# Receiver.net
KiCad netlist of a schematic drawn in Altium Designer
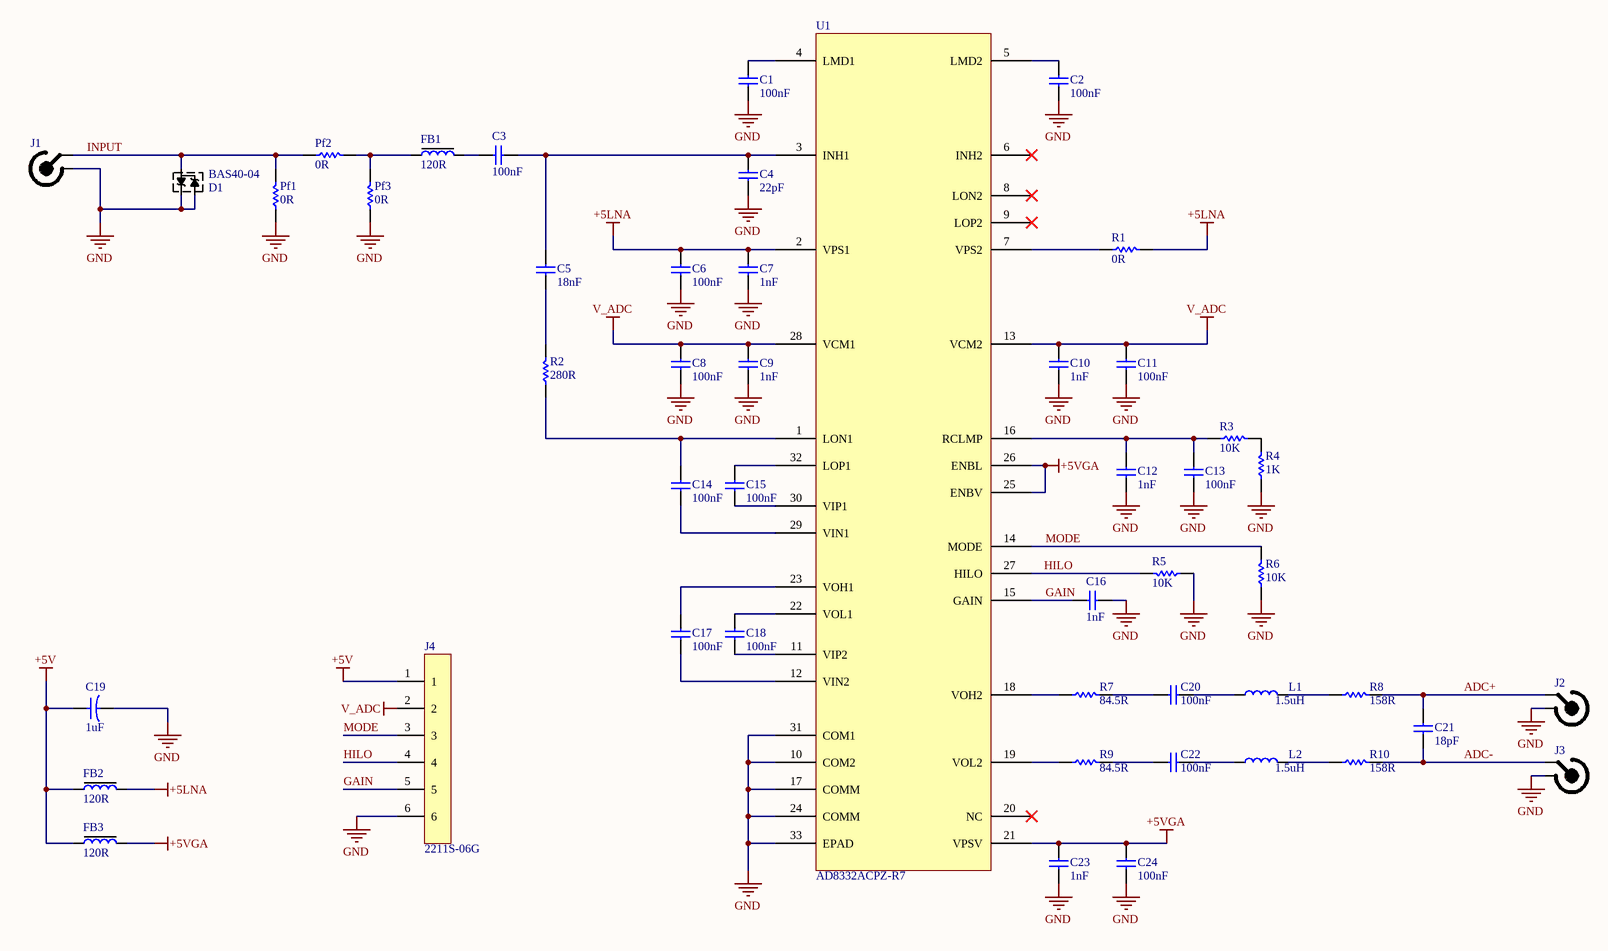
[diagram p0: Receiver.SchDoc]

(export (version "E")
  (design (tool "Eeschema 10.0.6"))
  (components
    (comp (ref "C1")
      (value "100nF")
      (footprint "CAP 0603/1608")
      (description "CAPACITOR 0603 100nF 10% 50V")
      (fields
        (field (name "MANUFACTURER") "Murata")
        (field (name "MANUFACTURER PART NUMBER") "GCJ188R71H104KA12D")
      )
      (libsource (lib "Component Library") (part "GCJ188R71H104KA12D"))
    )
    (comp (ref "C2")
      (value "100nF")
      (footprint "CAP 0603/1608")
      (description "CAPACITOR 0603 100nF 10% 50V")
      (fields
        (field (name "MANUFACTURER") "Murata")
        (field (name "MANUFACTURER PART NUMBER") "GCJ188R71H104KA12D")
      )
      (libsource (lib "Component Library") (part "GCJ188R71H104KA12D"))
    )
    (comp (ref "C3")
      (value "100nF")
      (footprint "CAP 0603/1608")
      (description "CAPACITOR 0603 100nF 10% 50V")
      (fields
        (field (name "MANUFACTURER") "Murata")
        (field (name "MANUFACTURER PART NUMBER") "GCJ188R71H104KA12D")
      )
      (libsource (lib "Component Library") (part "GCJ188R71H104KA12D"))
    )
    (comp (ref "C4")
      (value "22pF")
      (footprint "CAP 0603/1608")
      (description "CAPACITOR 0603 22 pF 50 V  5%, C0G / NP0")
      (fields
        (field (name "MANUFACTURER") "TDK")
        (field (name "MANUFACTURER PART NUMBER") "C1608C0G1H220J080AA")
      )
      (libsource (lib "Component Library") (part "C1608C0G1H220J080AA"))
    )
    (comp (ref "C5")
      (value "18nF")
      (footprint "CAP 0603/1608")
      (description "CAPACITOR 0603 18nF 35V NP0")
      (fields
        (field (name "MANUFACTURER") "TDK")
        (field (name "MANUFACTURER PART NUMBER") "C1608C0G1V183J080AC")
      )
      (libsource (lib "Component Library") (part "C1608C0G1V183J080AC"))
    )
    (comp (ref "C6")
      (value "100nF")
      (footprint "CAP 0603/1608")
      (description "CAPACITOR 0603 100nF 10% 50V")
      (fields
        (field (name "MANUFACTURER") "Murata")
        (field (name "MANUFACTURER PART NUMBER") "GCJ188R71H104KA12D")
      )
      (libsource (lib "Component Library") (part "GCJ188R71H104KA12D"))
    )
    (comp (ref "C7")
      (value "1nF")
      (footprint "CAP 0603/1608")
      (description "CAPACITOR 0603 1nF 100V C0G/NP0")
      (fields
        (field (name "MANUFACTURER") "Murata")
        (field (name "MANUFACTURER PART NUMBER") "GRM1885C2A102JA01D")
      )
      (libsource (lib "Component Library") (part "GRM1885C2A102JA01D"))
    )
    (comp (ref "C8")
      (value "100nF")
      (footprint "CAP 0603/1608")
      (description "CAPACITOR 0603 100nF 10% 50V")
      (fields
        (field (name "MANUFACTURER") "Murata")
        (field (name "MANUFACTURER PART NUMBER") "GCJ188R71H104KA12D")
      )
      (libsource (lib "Component Library") (part "GCJ188R71H104KA12D"))
    )
    (comp (ref "C9")
      (value "1nF")
      (footprint "CAP 0603/1608")
      (description "CAPACITOR 0603 1nF 100V C0G/NP0")
      (fields
        (field (name "MANUFACTURER") "Murata")
        (field (name "MANUFACTURER PART NUMBER") "GRM1885C2A102JA01D")
      )
      (libsource (lib "Component Library") (part "GRM1885C2A102JA01D"))
    )
    (comp (ref "C10")
      (value "1nF")
      (footprint "CAP 0603/1608")
      (description "CAPACITOR 0603 1nF 100V C0G/NP0")
      (fields
        (field (name "MANUFACTURER") "Murata")
        (field (name "MANUFACTURER PART NUMBER") "GRM1885C2A102JA01D")
      )
      (libsource (lib "Component Library") (part "GRM1885C2A102JA01D"))
    )
    (comp (ref "C11")
      (value "100nF")
      (footprint "CAP 0603/1608")
      (description "CAPACITOR 0603 100nF 10% 50V")
      (fields
        (field (name "MANUFACTURER") "Murata")
        (field (name "MANUFACTURER PART NUMBER") "GCJ188R71H104KA12D")
      )
      (libsource (lib "Component Library") (part "GCJ188R71H104KA12D"))
    )
    (comp (ref "C12")
      (value "1nF")
      (footprint "CAP 0603/1608")
      (description "CAPACITOR 0603 1nF 100V C0G/NP0")
      (fields
        (field (name "MANUFACTURER") "Murata")
        (field (name "MANUFACTURER PART NUMBER") "GRM1885C2A102JA01D")
      )
      (libsource (lib "Component Library") (part "GRM1885C2A102JA01D"))
    )
    (comp (ref "C13")
      (value "100nF")
      (footprint "CAP 0603/1608")
      (description "CAPACITOR 0603 100nF 10% 50V")
      (fields
        (field (name "MANUFACTURER") "Murata")
        (field (name "MANUFACTURER PART NUMBER") "GCJ188R71H104KA12D")
      )
      (libsource (lib "Component Library") (part "GCJ188R71H104KA12D"))
    )
    (comp (ref "C14")
      (value "100nF")
      (footprint "CAP 0603/1608")
      (description "CAPACITOR 0603 100nF 10% 50V")
      (fields
        (field (name "MANUFACTURER") "Murata")
        (field (name "MANUFACTURER PART NUMBER") "GCJ188R71H104KA12D")
      )
      (libsource (lib "Component Library") (part "GCJ188R71H104KA12D"))
    )
    (comp (ref "C15")
      (value "100nF")
      (footprint "CAP 0603/1608")
      (description "CAPACITOR 0603 100nF 10% 50V")
      (fields
        (field (name "MANUFACTURER") "Murata")
        (field (name "MANUFACTURER PART NUMBER") "GCJ188R71H104KA12D")
      )
      (libsource (lib "Component Library") (part "GCJ188R71H104KA12D"))
    )
    (comp (ref "C16")
      (value "1nF")
      (footprint "CAP 0603/1608")
      (description "CAPACITOR 0603 1nF 100V C0G/NP0")
      (fields
        (field (name "MANUFACTURER") "Murata")
        (field (name "MANUFACTURER PART NUMBER") "GRM1885C2A102JA01D")
      )
      (libsource (lib "Component Library") (part "GRM1885C2A102JA01D"))
    )
    (comp (ref "C17")
      (value "100nF")
      (footprint "CAP 0603/1608")
      (description "CAPACITOR 0603 100nF 10% 50V")
      (fields
        (field (name "MANUFACTURER") "Murata")
        (field (name "MANUFACTURER PART NUMBER") "GCJ188R71H104KA12D")
      )
      (libsource (lib "Component Library") (part "GCJ188R71H104KA12D"))
    )
    (comp (ref "C18")
      (value "100nF")
      (footprint "CAP 0603/1608")
      (description "CAPACITOR 0603 100nF 10% 50V")
      (fields
        (field (name "MANUFACTURER") "Murata")
        (field (name "MANUFACTURER PART NUMBER") "GCJ188R71H104KA12D")
      )
      (libsource (lib "Component Library") (part "GCJ188R71H104KA12D"))
    )
    (comp (ref "C19")
      (value "1uF")
      (footprint "CAP CASE A")
      (description "CAPACITOR TANT 1uF 16V")
      (fields
        (field (name "MANUFACTURER") "KEMET")
        (field (name "MANUFACTURER PART NUMBER") "T491A105K016AT")
      )
      (libsource (lib "Component Library") (part "T491A105K016AT"))
    )
    (comp (ref "C20")
      (value "100nF")
      (footprint "CAP 0603/1608")
      (description "CAPACITOR 0603 100nF 10% 50V")
      (fields
        (field (name "MANUFACTURER") "Murata")
        (field (name "MANUFACTURER PART NUMBER") "GCJ188R71H104KA12D")
      )
      (libsource (lib "Component Library") (part "GCJ188R71H104KA12D"))
    )
    (comp (ref "C21")
      (value "18pF")
      (footprint "CAP 0603/1608")
      (description "CAPACITOR 0603 18pF 50V C0G")
      (fields
        (field (name "MANUFACTURER") "TDK")
        (field (name "MANUFACTURER PART NUMBER") "C1608C0G1H180J080AA")
      )
      (libsource (lib "Component Library") (part "C1608C0G1H180J080AA"))
    )
    (comp (ref "C22")
      (value "100nF")
      (footprint "CAP 0603/1608")
      (description "CAPACITOR 0603 100nF 10% 50V")
      (fields
        (field (name "MANUFACTURER") "Murata")
        (field (name "MANUFACTURER PART NUMBER") "GCJ188R71H104KA12D")
      )
      (libsource (lib "Component Library") (part "GCJ188R71H104KA12D"))
    )
    (comp (ref "C23")
      (value "1nF")
      (footprint "CAP 0603/1608")
      (description "CAPACITOR 0603 1nF 100V C0G/NP0")
      (fields
        (field (name "MANUFACTURER") "Murata")
        (field (name "MANUFACTURER PART NUMBER") "GRM1885C2A102JA01D")
      )
      (libsource (lib "Component Library") (part "GRM1885C2A102JA01D"))
    )
    (comp (ref "C24")
      (value "100nF")
      (footprint "CAP 0603/1608")
      (description "CAPACITOR 0603 100nF 10% 50V")
      (fields
        (field (name "MANUFACTURER") "Murata")
        (field (name "MANUFACTURER PART NUMBER") "GCJ188R71H104KA12D")
      )
      (libsource (lib "Component Library") (part "GCJ188R71H104KA12D"))
    )
    (comp (ref "D1")
      (value "BAS40-04")
      (footprint "SOT-23-3")
      (description "SCHOTTKY DIODE")
      (fields (field (name "MANUFACTURER") "Infineon"))
      (libsource (lib "Component Library") (part "BAS40-04"))
    )
    (comp (ref "FB1")
      (value "120R")
      (footprint "FER 0805/2012")
      (description "FERRITE BEAD 120Ohm 3A")
      (fields
        (field (name "MANUFACTURER") "Murata")
        (field (name "MANUFACTURER PART NUMBER") "BLM21PG121SN1D")
      )
      (libsource (lib "Component Library") (part "BLM21PG121SN1D"))
    )
    (comp (ref "FB2")
      (value "120R")
      (footprint "FER 0805/2012")
      (description "FERRITE BEAD 120Ohm 3A")
      (fields
        (field (name "MANUFACTURER") "Murata")
        (field (name "MANUFACTURER PART NUMBER") "BLM21PG121SN1D")
      )
      (libsource (lib "Component Library") (part "BLM21PG121SN1D"))
    )
    (comp (ref "FB3")
      (value "120R")
      (footprint "FER 0805/2012")
      (description "FERRITE BEAD 120Ohm 3A")
      (fields
        (field (name "MANUFACTURER") "Murata")
        (field (name "MANUFACTURER PART NUMBER") "BLM21PG121SN1D")
      )
      (libsource (lib "Component Library") (part "BLM21PG121SN1D"))
    )
    (comp (ref "J1")
      (value "73251-1150")
      (footprint "73251-1150")
      (description "CONN SMA RCPT STR 50OHM EDGE MNT")
      (fields (field (name "MANUFACTURER") "Molex"))
      (libsource (lib "") (part "73251-1150_1"))
    )
    (comp (ref "J2")
      (value "73251-1150")
      (footprint "73251-1150")
      (description "CONN SMA RCPT STR 50OHM EDGE MNT")
      (fields (field (name "MANUFACTURER") "Molex"))
      (libsource (lib "Component Library") (part "73251-1150"))
    )
    (comp (ref "J3")
      (value "73251-1150")
      (footprint "73251-1150")
      (description "CONN SMA RCPT STR 50OHM EDGE MNT")
      (fields (field (name "MANUFACTURER") "Molex"))
      (libsource (lib "Component Library") (part "73251-1150"))
    )
    (comp (ref "J4")
      (value "2211S-06G")
      (footprint "HEADER 6-WAY 2.54 mm")
      (description "HEADER 6-Way 2.54mm TH")
      (fields (field (name "MANUFACTURER") "Multicomp"))
      (libsource (lib "Component Library") (part "2211S-06G"))
    )
    (comp (ref "L1")
      (value "1.5uH")
      (footprint "FER 0603/1608")
      (description "INDUCTOR 0603 1.5uH 10%")
      (fields (field (name "MANUFACTURER") "TDK") (field (name "MANUFACTURER PART NUMBER") "MLF1608A1R5K"))
      (libsource (lib "Component Library") (part "MLF1608A1R5K"))
    )
    (comp (ref "L2")
      (value "1.5uH")
      (footprint "FER 0603/1608")
      (description "INDUCTOR 0603 1.5uH 10%")
      (fields (field (name "MANUFACTURER") "TDK") (field (name "MANUFACTURER PART NUMBER") "MLF1608A1R5K"))
      (libsource (lib "Component Library") (part "MLF1608A1R5K"))
    )
    (comp (ref "Pf1")
      (value "0R")
      (footprint "RES 1206/3216")
      (description "RESISTOR 1206 0R")
      (fields
        (field (name "MANUFACTURER") "Panasonic")
        (field (name "MANUFACTURER PART NUMBER") "ERJ8GEY0R00V")
      )
      (libsource (lib "Component Library") (part "ERJ8GEY0R00V"))
    )
    (comp (ref "Pf2")
      (value "0R")
      (footprint "RES 1206/3216")
      (description "RESISTOR 1206 0R")
      (fields
        (field (name "MANUFACTURER") "Panasonic")
        (field (name "MANUFACTURER PART NUMBER") "ERJ8GEY0R00V")
      )
      (libsource (lib "Component Library") (part "ERJ8GEY0R00V"))
    )
    (comp (ref "Pf3")
      (value "0R")
      (footprint "RES 1206/3216")
      (description "RESISTOR 1206 0R")
      (fields
        (field (name "MANUFACTURER") "Panasonic")
        (field (name "MANUFACTURER PART NUMBER") "ERJ8GEY0R00V")
      )
      (libsource (lib "Component Library") (part "ERJ8GEY0R00V"))
    )
    (comp (ref "R1")
      (value "0R")
      (footprint "RES 0603/1608")
      (description "RESISTOR 0603 0R")
      (fields
        (field (name "MANUFACTURER") "Panasonic")
        (field (name "MANUFACTURER PART NUMBER") "ERJ-3GEY0R00V")
      )
      (libsource (lib "Component Library") (part "ERJ3GEY0R00V"))
    )
    (comp (ref "R2")
      (value "280R")
      (footprint "RES 0603/1608")
      (description "RESISTOR 0603 280R 1%")
      (fields
        (field (name "MANUFACTURER") "Panasonic")
        (field (name "MANUFACTURER PART NUMBER") "ERJ-3EKF2800V")
      )
      (libsource (lib "Component Library") (part "ERJ3EKF2800V"))
    )
    (comp (ref "R3")
      (value "10K")
      (footprint "RES 0603/1608")
      (description "RESISTOR 0603 10K 1%")
      (fields
        (field (name "MANUFACTURER") "Panasonic")
        (field (name "MANUFACTURER PART NUMBER") "ERJ3EKF1002V")
      )
      (libsource (lib "Component Library") (part "ERJ3EKF1002V"))
    )
    (comp (ref "R4")
      (value "1K")
      (footprint "RES 0603/1608")
      (description "RESISTOR 0603 1K 1%")
      (fields
        (field (name "MANUFACTURER") "Panasonic")
        (field (name "MANUFACTURER PART NUMBER") "ERJ3EKF1001V")
      )
      (libsource (lib "Component Library") (part "ERJ3EKF1001V"))
    )
    (comp (ref "R5")
      (value "10K")
      (footprint "RES 0603/1608")
      (description "RESISTOR 0603 10K 1%")
      (fields
        (field (name "MANUFACTURER") "Panasonic")
        (field (name "MANUFACTURER PART NUMBER") "ERJ3EKF1002V")
      )
      (libsource (lib "Component Library") (part "ERJ3EKF1002V"))
    )
    (comp (ref "R6")
      (value "10K")
      (footprint "RES 0603/1608")
      (description "RESISTOR 0603 10K 1%")
      (fields
        (field (name "MANUFACTURER") "Panasonic")
        (field (name "MANUFACTURER PART NUMBER") "ERJ3EKF1002V")
      )
      (libsource (lib "Component Library") (part "ERJ3EKF1002V"))
    )
    (comp (ref "R7")
      (value "84.5R")
      (footprint "RES 0603/1608")
      (description "RESISTOR 0603 84R5 1%")
      (fields
        (field (name "MANUFACTURER") "Panasonic")
        (field (name "MANUFACTURER PART NUMBER") "ERJ-3EKF84R5V")
      )
      (libsource (lib "Component Library") (part "ERJ3EKF84R5V"))
    )
    (comp (ref "R8")
      (value "158R")
      (footprint "RES 0603/1608")
      (description "RESISTOR 0603 158R 1%")
      (fields
        (field (name "MANUFACTURER") "Panasonic")
        (field (name "MANUFACTURER PART NUMBER") "ERJ-3EKF1580V")
      )
      (libsource (lib "Component Library") (part "ERJ3EKF1580V"))
    )
    (comp (ref "R9")
      (value "84.5R")
      (footprint "RES 0603/1608")
      (description "RESISTOR 0603 84R5 1%")
      (fields
        (field (name "MANUFACTURER") "Panasonic")
        (field (name "MANUFACTURER PART NUMBER") "ERJ-3EKF84R5V")
      )
      (libsource (lib "Component Library") (part "ERJ3EKF84R5V"))
    )
    (comp (ref "R10")
      (value "158R")
      (footprint "RES 0603/1608")
      (description "RESISTOR 0603 158R 1%")
      (fields
        (field (name "MANUFACTURER") "Panasonic")
        (field (name "MANUFACTURER PART NUMBER") "ERJ-3EKF1580V")
      )
      (libsource (lib "Component Library") (part "ERJ3EKF1580V"))
    )
    (comp (ref "U1")
      (value "AD8332ACPZ-R7")
      (footprint "LFCSP-32")
      (description "2-CHAN VGA 32LFCSP")
      (fields (field (name "MANUFACTURER") "Analog Devices"))
      (libsource (lib "Component Library") (part "AD8332ACPZ-R7"))
    )
  )
  (nets
    (net (code "1") (name "+5LNA") (class "Default")
      (node (ref "C6") (pin "1") (pinfunction "1_1") (pintype "passive"))
      (node (ref "C7") (pin "2") (pinfunction "2_2") (pintype "passive"))
      (node (ref "FB2") (pin "2") (pinfunction "2_2") (pintype "passive"))
      (node (ref "R1") (pin "2") (pintype "passive"))
      (node (ref "U1") (pin "2") (pinfunction "VPS1_2") (pintype "passive"))
    )
    (net (code "2") (name "+5V") (class "Default")
      (node (ref "C19") (pin "1") (pintype "passive"))
      (node (ref "FB2") (pin "1") (pinfunction "1_1") (pintype "passive"))
      (node (ref "FB3") (pin "1") (pinfunction "1_1") (pintype "passive"))
      (node (ref "J4") (pin "1") (pinfunction "1_1") (pintype "passive"))
    )
    (net (code "3") (name "+5VGA") (class "Default")
      (node (ref "C23") (pin "2") (pinfunction "2_2") (pintype "passive"))
      (node (ref "C24") (pin "2") (pinfunction "2_2") (pintype "passive"))
      (node (ref "FB3") (pin "2") (pinfunction "2_2") (pintype "passive"))
      (node (ref "U1") (pin "21") (pinfunction "VPSV_21") (pintype "passive"))
      (node (ref "U1") (pin "25") (pinfunction "ENBV_25") (pintype "passive"))
      (node (ref "U1") (pin "26") (pinfunction "ENBL_26") (pintype "passive"))
    )
    (net (code "4") (name "/ADC+") (class "Default")
      (node (ref "C21") (pin "2") (pinfunction "2_2") (pintype "passive"))
      (node (ref "J2") (pin "1") (pinfunction "1_1") (pintype "passive"))
      (node (ref "R8") (pin "2") (pintype "passive"))
    )
    (net (code "5") (name "/ADC-") (class "Default")
      (node (ref "C21") (pin "1") (pinfunction "1_1") (pintype "passive"))
      (node (ref "J3") (pin "1") (pinfunction "1_1") (pintype "passive"))
      (node (ref "R10") (pin "2") (pintype "passive"))
    )
    (net (code "6") (name "/GAIN") (class "Default")
      (node (ref "C16") (pin "2") (pinfunction "2_2") (pintype "passive"))
      (node (ref "J4") (pin "5") (pinfunction "5_5") (pintype "passive"))
      (node (ref "U1") (pin "15") (pinfunction "GAIN_15") (pintype "passive"))
    )
    (net (code "7") (name "/HILO") (class "Default")
      (node (ref "J4") (pin "4") (pinfunction "4_4") (pintype "passive"))
      (node (ref "R5") (pin "2") (pintype "passive"))
      (node (ref "U1") (pin "27") (pinfunction "HILO_27") (pintype "passive"))
    )
    (net (code "8") (name "/INPUT") (class "Default")
      (node (ref "D1") (pin "3") (pinfunction "3_3") (pintype "passive"))
      (node (ref "J1") (pin "1") (pinfunction "1_1") (pintype "passive"))
      (node (ref "Pf1") (pin "2") (pintype "passive"))
      (node (ref "Pf2") (pin "1") (pintype "passive"))
    )
    (net (code "9") (name "/MODE") (class "Default")
      (node (ref "J4") (pin "3") (pinfunction "3_3") (pintype "passive"))
      (node (ref "R6") (pin "2") (pintype "passive"))
      (node (ref "U1") (pin "14") (pinfunction "MODE_14") (pintype "passive"))
    )
    (net (code "10") (name "GND") (class "Default")
      (node (ref "C1") (pin "1") (pinfunction "1_1") (pintype "passive"))
      (node (ref "C10") (pin "1") (pinfunction "1_1") (pintype "passive"))
      (node (ref "C11") (pin "2") (pinfunction "2_2") (pintype "passive"))
      (node (ref "C12") (pin "1") (pinfunction "1_1") (pintype "passive"))
      (node (ref "C13") (pin "1") (pinfunction "1_1") (pintype "passive"))
      (node (ref "C16") (pin "1") (pinfunction "1_1") (pintype "passive"))
      (node (ref "C19") (pin "2") (pintype "passive"))
      (node (ref "C2") (pin "1") (pinfunction "1_1") (pintype "passive"))
      (node (ref "C23") (pin "1") (pinfunction "1_1") (pintype "passive"))
      (node (ref "C24") (pin "1") (pinfunction "1_1") (pintype "passive"))
      (node (ref "C4") (pin "1") (pinfunction "1_1") (pintype "passive"))
      (node (ref "C6") (pin "2") (pinfunction "2_2") (pintype "passive"))
      (node (ref "C7") (pin "1") (pinfunction "1_1") (pintype "passive"))
      (node (ref "C8") (pin "2") (pinfunction "2_2") (pintype "passive"))
      (node (ref "C9") (pin "1") (pinfunction "1_1") (pintype "passive"))
      (node (ref "D1") (pin "1") (pinfunction "1_1") (pintype "passive"))
      (node (ref "D1") (pin "2") (pinfunction "2_2") (pintype "passive"))
      (node (ref "J1") (pin "2") (pinfunction "2_2") (pintype "passive"))
      (node (ref "J2") (pin "2") (pinfunction "2_2") (pintype "passive"))
      (node (ref "J3") (pin "2") (pinfunction "2_2") (pintype "passive"))
      (node (ref "J4") (pin "6") (pinfunction "6_6") (pintype "passive"))
      (node (ref "Pf1") (pin "1") (pintype "passive"))
      (node (ref "Pf3") (pin "1") (pintype "passive"))
      (node (ref "R4") (pin "1") (pintype "passive"))
      (node (ref "R5") (pin "1") (pintype "passive"))
      (node (ref "R6") (pin "1") (pintype "passive"))
      (node (ref "U1") (pin "10") (pinfunction "COM2_10") (pintype "passive"))
      (node (ref "U1") (pin "17") (pinfunction "COMM_17") (pintype "passive"))
      (node (ref "U1") (pin "24") (pinfunction "COMM_24") (pintype "passive"))
      (node (ref "U1") (pin "31") (pinfunction "COM1_31") (pintype "passive"))
      (node (ref "U1") (pin "33") (pinfunction "EPAD_33") (pintype "passive"))
    )
    (net (code "11") (name "Net-(C3-Pad1)") (class "Default")
      (node (ref "C3") (pin "1") (pinfunction "1_1") (pintype "passive"))
      (node (ref "FB1") (pin "2") (pinfunction "2_2") (pintype "passive"))
    )
    (net (code "12") (name "Net-(C5-Pad1)") (class "Default")
      (node (ref "C5") (pin "1") (pinfunction "1_1") (pintype "passive"))
      (node (ref "R2") (pin "2") (pintype "passive"))
    )
    (net (code "13") (name "Net-(C20-Pad1)") (class "Default")
      (node (ref "C20") (pin "1") (pinfunction "1_1") (pintype "passive"))
      (node (ref "R7") (pin "2") (pintype "passive"))
    )
    (net (code "14") (name "Net-(C20-Pad2)") (class "Default")
      (node (ref "C20") (pin "2") (pinfunction "2_2") (pintype "passive"))
      (node (ref "L1") (pin "1") (pinfunction "1_1") (pintype "passive"))
    )
    (net (code "15") (name "Net-(C22-Pad1)") (class "Default")
      (node (ref "C22") (pin "1") (pinfunction "1_1") (pintype "passive"))
      (node (ref "R9") (pin "2") (pintype "passive"))
    )
    (net (code "16") (name "Net-(C22-Pad2)") (class "Default")
      (node (ref "C22") (pin "2") (pinfunction "2_2") (pintype "passive"))
      (node (ref "L2") (pin "1") (pinfunction "1_1") (pintype "passive"))
    )
    (net (code "17") (name "Net-(FB1-Pad1)") (class "Default")
      (node (ref "FB1") (pin "1") (pinfunction "1_1") (pintype "passive"))
      (node (ref "Pf2") (pin "2") (pintype "passive"))
      (node (ref "Pf3") (pin "2") (pintype "passive"))
    )
    (net (code "18") (name "Net-(L1-Pad2)") (class "Default")
      (node (ref "L1") (pin "2") (pinfunction "2_2") (pintype "passive"))
      (node (ref "R8") (pin "1") (pintype "passive"))
    )
    (net (code "19") (name "Net-(L2-Pad2)") (class "Default")
      (node (ref "L2") (pin "2") (pinfunction "2_2") (pintype "passive"))
      (node (ref "R10") (pin "1") (pintype "passive"))
    )
    (net (code "20") (name "Net-(R3-Pad2)") (class "Default")
      (node (ref "R3") (pin "2") (pintype "passive"))
      (node (ref "R4") (pin "2") (pintype "passive"))
    )
    (net (code "21") (name "Net-(U1-INH1)") (class "Default")
      (node (ref "C3") (pin "2") (pinfunction "2_2") (pintype "passive"))
      (node (ref "C4") (pin "2") (pinfunction "2_2") (pintype "passive"))
      (node (ref "C5") (pin "2") (pinfunction "2_2") (pintype "passive"))
      (node (ref "U1") (pin "3") (pinfunction "INH1_3") (pintype "passive"))
    )
    (net (code "22") (name "Net-(U1-LMD1)") (class "Default")
      (node (ref "C1") (pin "2") (pinfunction "2_2") (pintype "passive"))
      (node (ref "U1") (pin "4") (pinfunction "LMD1_4") (pintype "passive"))
    )
    (net (code "23") (name "Net-(U1-LMD2)") (class "Default")
      (node (ref "C2") (pin "2") (pinfunction "2_2") (pintype "passive"))
      (node (ref "U1") (pin "5") (pinfunction "LMD2_5") (pintype "passive"))
    )
    (net (code "24") (name "Net-(U1-LON1)") (class "Default")
      (node (ref "C14") (pin "2") (pinfunction "2_2") (pintype "passive"))
      (node (ref "R2") (pin "1") (pintype "passive"))
      (node (ref "U1") (pin "1") (pinfunction "LON1_1") (pintype "passive"))
    )
    (net (code "25") (name "Net-(U1-LOP1)") (class "Default")
      (node (ref "C15") (pin "2") (pinfunction "2_2") (pintype "passive"))
      (node (ref "U1") (pin "32") (pinfunction "LOP1_32") (pintype "passive"))
    )
    (net (code "26") (name "Net-(U1-RCLMP)") (class "Default")
      (node (ref "C12") (pin "2") (pinfunction "2_2") (pintype "passive"))
      (node (ref "C13") (pin "2") (pinfunction "2_2") (pintype "passive"))
      (node (ref "R3") (pin "1") (pintype "passive"))
      (node (ref "U1") (pin "16") (pinfunction "RCLMP_16") (pintype "passive"))
    )
    (net (code "27") (name "Net-(U1-VIN1)") (class "Default")
      (node (ref "C14") (pin "1") (pinfunction "1_1") (pintype "passive"))
      (node (ref "U1") (pin "29") (pinfunction "VIN1_29") (pintype "passive"))
    )
    (net (code "28") (name "Net-(U1-VIN2)") (class "Default")
      (node (ref "C17") (pin "1") (pinfunction "1_1") (pintype "passive"))
      (node (ref "U1") (pin "12") (pinfunction "VIN2_12") (pintype "passive"))
    )
    (net (code "29") (name "Net-(U1-VIP1)") (class "Default")
      (node (ref "C15") (pin "1") (pinfunction "1_1") (pintype "passive"))
      (node (ref "U1") (pin "30") (pinfunction "VIP1_30") (pintype "passive"))
    )
    (net (code "30") (name "Net-(U1-VIP2)") (class "Default")
      (node (ref "C18") (pin "1") (pinfunction "1_1") (pintype "passive"))
      (node (ref "U1") (pin "11") (pinfunction "VIP2_11") (pintype "passive"))
    )
    (net (code "31") (name "Net-(U1-VOH1)") (class "Default")
      (node (ref "C17") (pin "2") (pinfunction "2_2") (pintype "passive"))
      (node (ref "U1") (pin "23") (pinfunction "VOH1_23") (pintype "passive"))
    )
    (net (code "32") (name "Net-(U1-VOH2)") (class "Default")
      (node (ref "R7") (pin "1") (pintype "passive"))
      (node (ref "U1") (pin "18") (pinfunction "VOH2_18") (pintype "passive"))
    )
    (net (code "33") (name "Net-(U1-VOL1)") (class "Default")
      (node (ref "C18") (pin "2") (pinfunction "2_2") (pintype "passive"))
      (node (ref "U1") (pin "22") (pinfunction "VOL1_22") (pintype "passive"))
    )
    (net (code "34") (name "Net-(U1-VOL2)") (class "Default")
      (node (ref "R9") (pin "1") (pintype "passive"))
      (node (ref "U1") (pin "19") (pinfunction "VOL2_19") (pintype "passive"))
    )
    (net (code "35") (name "Net-(U1-VPS2)") (class "Default")
      (node (ref "R1") (pin "1") (pintype "passive"))
      (node (ref "U1") (pin "7") (pinfunction "VPS2_7") (pintype "passive"))
    )
    (net (code "36") (name "V_ADC") (class "Default")
      (node (ref "C10") (pin "2") (pinfunction "2_2") (pintype "passive"))
      (node (ref "C11") (pin "1") (pinfunction "1_1") (pintype "passive"))
      (node (ref "C8") (pin "1") (pinfunction "1_1") (pintype "passive"))
      (node (ref "C9") (pin "2") (pinfunction "2_2") (pintype "passive"))
      (node (ref "J4") (pin "2") (pinfunction "2_2") (pintype "passive"))
      (node (ref "U1") (pin "13") (pinfunction "VCM2_13") (pintype "passive"))
      (node (ref "U1") (pin "28") (pinfunction "VCM1_28") (pintype "passive"))
    )
    (net (code "37") (name "unconnected-(U1-INH2-Pad6)") (class "Default")
      (node (ref "U1") (pin "6") (pinfunction "INH2_6") (pintype "passive+no_connect"))
    )
    (net (code "38") (name "unconnected-(U1-LON2-Pad8)") (class "Default")
      (node (ref "U1") (pin "8") (pinfunction "LON2_8") (pintype "passive+no_connect"))
    )
    (net (code "39") (name "unconnected-(U1-LOP2-Pad9)") (class "Default")
      (node (ref "U1") (pin "9") (pinfunction "LOP2_9") (pintype "passive+no_connect"))
    )
    (net (code "40") (name "unconnected-(U1-NC-Pad20)") (class "Default")
      (node (ref "U1") (pin "20") (pinfunction "NC_20") (pintype "passive+no_connect"))
    )
  )
)
